# Rx.net
KiCad netlist of a schematic drawn in Altium Designer
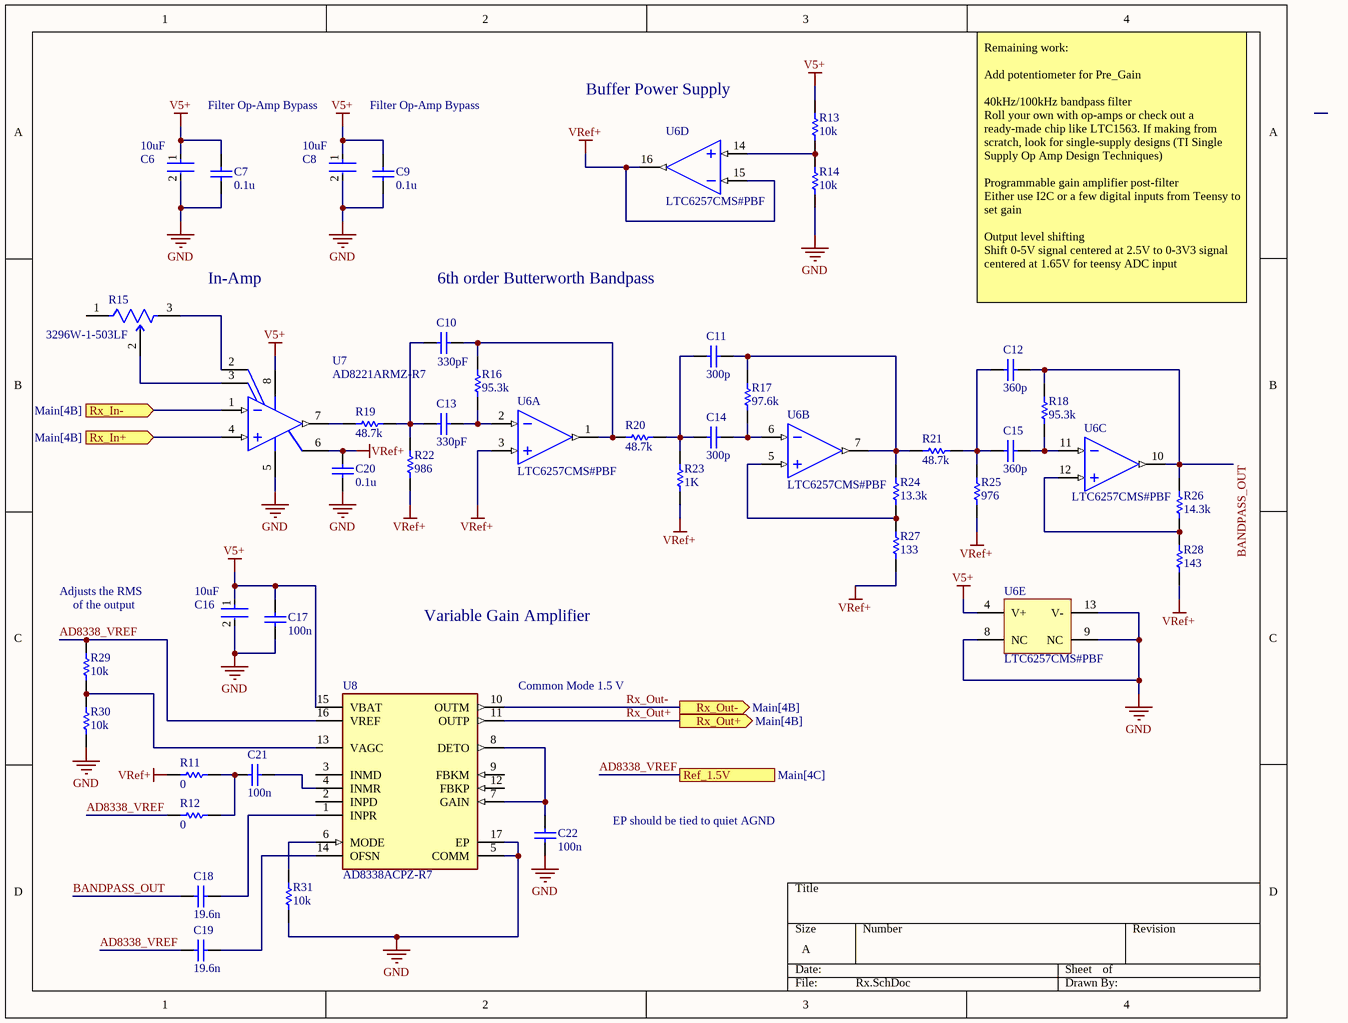
[diagram p0: Rx.SchDoc]

(export (version "E")
  (design (tool "Eeschema 10.0.6"))
  (components
    (comp (ref "C6")
      (value "C3216X5R1H106K160AB")
      (footprint "FP-C3216-160-0_2-IPC_A")
      (description "Multilayer Ceramic Capacitors 10uF ±10% 50V X5R SMD 1206")
      (fields
        (field (name "TOLERANCE") "10%")
        (field (name "VOLTAGE") "50V")
        (field (name "CAPACITANCE") "10uF")
      )
      (libsource (lib "Altium Content Vault") (part "11868f565c42a9108669ba33697ecf6"))
    )
    (comp (ref "C7")
      (value "0.1u")
      (footprint "0805")
      (description "Capacitor")
      (libsource (lib "Simulation Generic Components") (part "Capacitor"))
    )
    (comp (ref "C8")
      (value "C3216X5R1H106K160AB")
      (footprint "FP-C3216-160-0_2-IPC_A")
      (description "Multilayer Ceramic Capacitors 10uF ±10% 50V X5R SMD 1206")
      (fields
        (field (name "TOLERANCE") "10%")
        (field (name "VOLTAGE") "50V")
        (field (name "CAPACITANCE") "10uF")
      )
      (libsource (lib "Altium Content Vault") (part "11868f565c42a9108669ba33697ecf6"))
    )
    (comp (ref "C9")
      (value "0.1u")
      (footprint "0805")
      (description "Capacitor")
      (libsource (lib "Simulation Generic Components") (part "Capacitor"))
    )
    (comp (ref "C10")
      (value "330pF")
      (footprint "0805")
      (description "Capacitor")
      (libsource (lib "Simulation Generic Components") (part "Capacitor"))
    )
    (comp (ref "C11")
      (value "300p")
      (footprint "0805")
      (description "Capacitor")
      (libsource (lib "Simulation Generic Components") (part "Capacitor"))
    )
    (comp (ref "C12")
      (value "360p")
      (footprint "0805")
      (description "Capacitor")
      (libsource (lib "Simulation Generic Components") (part "Capacitor"))
    )
    (comp (ref "C13")
      (value "330pF")
      (footprint "0805")
      (description "Capacitor")
      (libsource (lib "Simulation Generic Components") (part "Capacitor"))
    )
    (comp (ref "C14")
      (value "300p")
      (footprint "0805")
      (description "Capacitor")
      (libsource (lib "Simulation Generic Components") (part "Capacitor"))
    )
    (comp (ref "C15")
      (value "360p")
      (footprint "0805")
      (description "Capacitor")
      (libsource (lib "Simulation Generic Components") (part "Capacitor"))
    )
    (comp (ref "C16")
      (value "C3216X5R1H106K160AB")
      (footprint "FP-C3216-160-0_2-IPC_A")
      (description "Multilayer Ceramic Capacitors 10uF ±10% 50V X5R SMD 1206")
      (fields
        (field (name "TOLERANCE") "10%")
        (field (name "VOLTAGE") "50V")
        (field (name "CAPACITANCE") "10uF")
      )
      (libsource (lib "Altium Content Vault") (part "11868f565c42a9108669ba33697ecf6"))
    )
    (comp (ref "C17")
      (value "100n")
      (footprint "0805")
      (description "Capacitor")
      (libsource (lib "Simulation Generic Components") (part "Capacitor"))
    )
    (comp (ref "C18")
      (value "19.6n")
      (footprint "0805")
      (description "Capacitor")
      (libsource (lib "Simulation Generic Components") (part "Capacitor"))
    )
    (comp (ref "C19")
      (value "19.6n")
      (footprint "0805")
      (description "Capacitor")
      (libsource (lib "Simulation Generic Components") (part "Capacitor"))
    )
    (comp (ref "C20")
      (value "0.1u")
      (footprint "0805")
      (description "Capacitor")
      (libsource (lib "Simulation Generic Components") (part "Capacitor"))
    )
    (comp (ref "C21")
      (value "100n")
      (footprint "0805")
      (description "Capacitor")
      (libsource (lib "Simulation Generic Components") (part "Capacitor"))
    )
    (comp (ref "C22")
      (value "100n")
      (footprint "0805")
      (description "Capacitor")
      (libsource (lib "Simulation Generic Components") (part "Capacitor"))
    )
    (comp (ref "R11")
      (value "0")
      (footprint "0805")
      (description "Resistor")
      (libsource (lib "Simulation Generic Components") (part "Resistor"))
    )
    (comp (ref "R12")
      (value "0")
      (footprint "0805")
      (description "Resistor")
      (libsource (lib "Simulation Generic Components") (part "Resistor"))
    )
    (comp (ref "R13")
      (value "10k")
      (footprint "0805")
      (description "Resistor")
      (libsource (lib "Simulation Generic Components") (part "Resistor"))
    )
    (comp (ref "R14")
      (value "10k")
      (footprint "0805")
      (description "Resistor")
      (libsource (lib "Simulation Generic Components") (part "Resistor"))
    )
    (comp (ref "R15")
      (value "3296W-1-503LF")
      (footprint "FP-3296W-MFG")
      (description "TRIMMER 50K OHM 0.5W PC PIN TOP")
      (fields (field (name "TOLERANCE") "10%"))
      (libsource (lib "Altium Content Vault") (part "2dcfd2547301a7d3209a5e99acfd772"))
    )
    (comp (ref "R16")
      (value "95.3k")
      (footprint "0805")
      (description "Resistor")
      (libsource (lib "Simulation Generic Components") (part "Resistor"))
    )
    (comp (ref "R17")
      (value "97.6k")
      (footprint "0805")
      (description "Resistor")
      (libsource (lib "Simulation Generic Components") (part "Resistor"))
    )
    (comp (ref "R18")
      (value "95.3k")
      (footprint "0805")
      (description "Resistor")
      (libsource (lib "Simulation Generic Components") (part "Resistor"))
    )
    (comp (ref "R19")
      (value "48.7k")
      (footprint "0805")
      (fields
        (field (name "MANUFACTURER") "Panasonic")
        (field (name "MANUFACTURER PART NUMBER") "ERJ-6ENF4872V")
        (field (name "TOLERANCE") "1%")
      )
      (libsource (lib "Simulation Generic Components") (part "Resistor"))
    )
    (comp (ref "R20")
      (value "48.7k")
      (footprint "0805")
      (fields
        (field (name "MANUFACTURER") "Panasonic")
        (field (name "MANUFACTURER PART NUMBER") "ERJ-6ENF4872V")
        (field (name "TOLERANCE") "1%")
      )
      (libsource (lib "Simulation Generic Components") (part "Resistor"))
    )
    (comp (ref "R21")
      (value "48.7k")
      (footprint "0805")
      (description "Resistor")
      (libsource (lib "Simulation Generic Components") (part "Resistor"))
    )
    (comp (ref "R22")
      (value "986")
      (footprint "0805")
      (description "Resistor")
      (libsource (lib "Simulation Generic Components") (part "Resistor"))
    )
    (comp (ref "R23")
      (value "1K")
      (footprint "0805")
      (description "Resistor")
      (libsource (lib "Simulation Generic Components") (part "Resistor"))
    )
    (comp (ref "R24")
      (value "13.3k")
      (footprint "0805")
      (description "Resistor")
      (libsource (lib "Simulation Generic Components") (part "Resistor"))
    )
    (comp (ref "R25")
      (value "976")
      (footprint "0805")
      (description "Resistor")
      (libsource (lib "Simulation Generic Components") (part "Resistor"))
    )
    (comp (ref "R26")
      (value "14.3k")
      (footprint "0805")
      (description "Resistor")
      (libsource (lib "Simulation Generic Components") (part "Resistor"))
    )
    (comp (ref "R27")
      (value "133")
      (footprint "0805")
      (description "Resistor")
      (libsource (lib "Simulation Generic Components") (part "Resistor"))
    )
    (comp (ref "R28")
      (value "143")
      (footprint "0805")
      (description "Resistor")
      (libsource (lib "Simulation Generic Components") (part "Resistor"))
    )
    (comp (ref "R29")
      (value "10k")
      (footprint "0805")
      (description "Resistor")
      (libsource (lib "Simulation Generic Components") (part "Resistor"))
    )
    (comp (ref "R30")
      (value "10k")
      (footprint "0805")
      (description "Resistor")
      (libsource (lib "Simulation Generic Components") (part "Resistor"))
    )
    (comp (ref "R31")
      (value "10k")
      (footprint "0805")
      (description "Resistor")
      (libsource (lib "Simulation Generic Components") (part "Resistor"))
    )
    (comp (ref "U6")
      (value "LTC6257CMS#PBF")
      (footprint "LT-MS-16_N")
      (fields
        (field (name "MANUFACTURER") "Linear Technology")
        (field (name "LINEAR TECHNOLOGY PART NUMBER") "LTC6257")
        (field (name "MANUFACTURER PART NUMBER") "ERJ-6ENF4872V")
      )
      (libsource (lib "") (part "LT-LTC608X-LTC607X-16_1"))
    )
    (comp (ref "U7")
      (value "AD8221ARMZ-R7")
      (footprint "ADI-RM-8_L")
      (fields (field (name "MANUFACTURER") "Analog Devices"))
      (libsource (lib "Altium Content Vault") (part "ADI-AD8221-8"))
    )
    (comp (ref "U8")
      (value "AD8338ACPZ-R7")
      (footprint "FP-CP-16-22-IPC_C")
      (description "IC OPAMP VGA 1 CIRCUIT 16LFCSP")
      (fields
        (field (name "OCTOPART") "https://octopart.com/ad8338acpz-r7-analog+devices-21054770")
        (field (name "MANUFACTURER") "Analog Devices")
      )
      (libsource (lib "Altium Content Vault") (part "4ce7887af0b7713ffabab50ab6d8fb3"))
    )
  )
  (nets
    (net (code "1") (name "/AD8338_VREF") (class "Default")
      (node (ref "C19") (pin "2") (pinfunction "2_2") (pintype "passive"))
      (node (ref "R12") (pin "2") (pinfunction "2_2") (pintype "passive"))
      (node (ref "R29") (pin "2") (pinfunction "2_2") (pintype "passive"))
      (node (ref "U8") (pin "16") (pinfunction "VREF_16") (pintype "power_in"))
    )
    (net (code "2") (name "/BANDPASS_OUT") (class "Default")
      (node (ref "C12") (pin "1") (pinfunction "1_1") (pintype "passive"))
      (node (ref "C18") (pin "2") (pinfunction "2_2") (pintype "passive"))
      (node (ref "R18") (pin "2") (pinfunction "2_2") (pintype "passive"))
      (node (ref "R26") (pin "2") (pinfunction "2_2") (pintype "passive"))
      (node (ref "U6") (pin "10") (pinfunction "OUT_C_10") (pintype "output"))
    )
    (net (code "3") (name "/Rx_In+") (class "Default")
      (node (ref "U7") (pin "4") (pinfunction "IN+_4") (pintype "input"))
    )
    (net (code "4") (name "/Rx_In-") (class "Default")
      (node (ref "U7") (pin "1") (pinfunction "IN-_1") (pintype "input"))
    )
    (net (code "5") (name "/Rx_Out+") (class "Default")
      (node (ref "U8") (pin "11") (pinfunction "OUTP_11") (pintype "output"))
    )
    (net (code "6") (name "/Rx_Out-") (class "Default")
      (node (ref "U8") (pin "10") (pinfunction "OUTM_10") (pintype "output"))
    )
    (net (code "7") (name "GND") (class "Default")
      (node (ref "C16") (pin "2") (pinfunction "2_2") (pintype "passive"))
      (node (ref "C17") (pin "1") (pinfunction "1_1") (pintype "passive"))
      (node (ref "C20") (pin "1") (pinfunction "1_1") (pintype "passive"))
      (node (ref "C22") (pin "1") (pinfunction "1_1") (pintype "passive"))
      (node (ref "C6") (pin "2") (pinfunction "2_2") (pintype "passive"))
      (node (ref "C7") (pin "1") (pinfunction "1_1") (pintype "passive"))
      (node (ref "C8") (pin "2") (pinfunction "2_2") (pintype "passive"))
      (node (ref "C9") (pin "1") (pinfunction "1_1") (pintype "passive"))
      (node (ref "R14") (pin "1") (pinfunction "1_1") (pintype "passive"))
      (node (ref "R30") (pin "1") (pinfunction "1_1") (pintype "passive"))
      (node (ref "R31") (pin "1") (pinfunction "1_1") (pintype "passive"))
      (node (ref "U6") (pin "13") (pinfunction "V-_13") (pintype "power_in"))
      (node (ref "U6") (pin "8") (pinfunction "NC_8") (pintype "passive"))
      (node (ref "U6") (pin "9") (pinfunction "NC_9") (pintype "passive"))
      (node (ref "U7") (pin "5") (pinfunction "VS-_5") (pintype "power_in"))
      (node (ref "U8") (pin "17") (pinfunction "EP_17") (pintype "power_in"))
      (node (ref "U8") (pin "5") (pinfunction "COMM_5") (pintype "power_in"))
    )
    (net (code "8") (name "Net-(C10-Pad2)") (class "Default")
      (node (ref "C10") (pin "2") (pinfunction "2_2") (pintype "passive"))
      (node (ref "C13") (pin "2") (pinfunction "2_2") (pintype "passive"))
      (node (ref "R19") (pin "2") (pinfunction "2_2") (pintype "passive"))
      (node (ref "R22") (pin "2") (pinfunction "2_2") (pintype "passive"))
    )
    (net (code "9") (name "Net-(C11-Pad2)") (class "Default")
      (node (ref "C11") (pin "2") (pinfunction "2_2") (pintype "passive"))
      (node (ref "C14") (pin "2") (pinfunction "2_2") (pintype "passive"))
      (node (ref "R20") (pin "2") (pinfunction "2_2") (pintype "passive"))
      (node (ref "R23") (pin "2") (pinfunction "2_2") (pintype "passive"))
    )
    (net (code "10") (name "Net-(C12-Pad2)") (class "Default")
      (node (ref "C12") (pin "2") (pinfunction "2_2") (pintype "passive"))
      (node (ref "C15") (pin "2") (pinfunction "2_2") (pintype "passive"))
      (node (ref "R21") (pin "2") (pinfunction "2_2") (pintype "passive"))
      (node (ref "R25") (pin "2") (pinfunction "2_2") (pintype "passive"))
    )
    (net (code "11") (name "Net-(C21-Pad2)") (class "Default")
      (node (ref "C21") (pin "2") (pinfunction "2_2") (pintype "passive"))
      (node (ref "R11") (pin "1") (pinfunction "1_1") (pintype "passive"))
      (node (ref "R12") (pin "1") (pinfunction "1_1") (pintype "passive"))
    )
    (net (code "12") (name "Net-(R15-CW)") (class "Default")
      (node (ref "R15") (pin "3") (pinfunction "CW_3") (pintype "passive"))
      (node (ref "U7") (pin "2") (pinfunction "RG_2") (pintype "passive"))
    )
    (net (code "13") (name "Net-(R15-WIPER)") (class "Default")
      (node (ref "R15") (pin "2") (pinfunction "WIPER_2") (pintype "passive"))
      (node (ref "U7") (pin "3") (pinfunction "RG_3") (pintype "passive"))
    )
    (net (code "14") (name "Net-(U6A-IN-_A)") (class "Default")
      (node (ref "C13") (pin "1") (pinfunction "1_1") (pintype "passive"))
      (node (ref "R16") (pin "1") (pinfunction "1_1") (pintype "passive"))
      (node (ref "U6") (pin "2") (pinfunction "IN-_A_2") (pintype "input"))
    )
    (net (code "15") (name "Net-(U6A-OUT_A)") (class "Default")
      (node (ref "C10") (pin "1") (pinfunction "1_1") (pintype "passive"))
      (node (ref "R16") (pin "2") (pinfunction "2_2") (pintype "passive"))
      (node (ref "R20") (pin "1") (pinfunction "1_1") (pintype "passive"))
      (node (ref "U6") (pin "1") (pinfunction "OUT_A_1") (pintype "output"))
    )
    (net (code "16") (name "Net-(U6B-IN+_B)") (class "Default")
      (node (ref "R24") (pin "1") (pinfunction "1_1") (pintype "passive"))
      (node (ref "R27") (pin "2") (pinfunction "2_2") (pintype "passive"))
      (node (ref "U6") (pin "5") (pinfunction "IN+_B_5") (pintype "input"))
    )
    (net (code "17") (name "Net-(U6B-IN-_B)") (class "Default")
      (node (ref "C14") (pin "1") (pinfunction "1_1") (pintype "passive"))
      (node (ref "R17") (pin "1") (pinfunction "1_1") (pintype "passive"))
      (node (ref "U6") (pin "6") (pinfunction "IN-_B_6") (pintype "input"))
    )
    (net (code "18") (name "Net-(U6B-OUT_B)") (class "Default")
      (node (ref "C11") (pin "1") (pinfunction "1_1") (pintype "passive"))
      (node (ref "R17") (pin "2") (pinfunction "2_2") (pintype "passive"))
      (node (ref "R21") (pin "1") (pinfunction "1_1") (pintype "passive"))
      (node (ref "R24") (pin "2") (pinfunction "2_2") (pintype "passive"))
      (node (ref "U6") (pin "7") (pinfunction "OUT_B_7") (pintype "output"))
    )
    (net (code "19") (name "Net-(U6C-IN+_C)") (class "Default")
      (node (ref "R26") (pin "1") (pinfunction "1_1") (pintype "passive"))
      (node (ref "R28") (pin "2") (pinfunction "2_2") (pintype "passive"))
      (node (ref "U6") (pin "12") (pinfunction "IN+_C_12") (pintype "input"))
    )
    (net (code "20") (name "Net-(U6C-IN-_C)") (class "Default")
      (node (ref "C15") (pin "1") (pinfunction "1_1") (pintype "passive"))
      (node (ref "R18") (pin "1") (pinfunction "1_1") (pintype "passive"))
      (node (ref "U6") (pin "11") (pinfunction "IN-_C_11") (pintype "input"))
    )
    (net (code "21") (name "Net-(U6D-IN+_D)") (class "Default")
      (node (ref "R13") (pin "1") (pinfunction "1_1") (pintype "passive"))
      (node (ref "R14") (pin "2") (pinfunction "2_2") (pintype "passive"))
      (node (ref "U6") (pin "14") (pinfunction "IN+_D_14") (pintype "input"))
    )
    (net (code "22") (name "Net-(U7-VOUT)") (class "Default")
      (node (ref "R19") (pin "1") (pinfunction "1_1") (pintype "passive"))
      (node (ref "U7") (pin "7") (pinfunction "VOUT_7") (pintype "output"))
    )
    (net (code "23") (name "Net-(U8-DETO)") (class "Default")
      (node (ref "C22") (pin "2") (pinfunction "2_2") (pintype "passive"))
      (node (ref "U8") (pin "7") (pinfunction "GAIN_7") (pintype "input"))
      (node (ref "U8") (pin "8") (pinfunction "DETO_8") (pintype "output"))
    )
    (net (code "24") (name "Net-(U8-INMR)") (class "Default")
      (node (ref "C21") (pin "1") (pinfunction "1_1") (pintype "passive"))
      (node (ref "U8") (pin "4") (pinfunction "INMR_4") (pintype "passive"))
    )
    (net (code "25") (name "Net-(U8-INPR)") (class "Default")
      (node (ref "C18") (pin "1") (pinfunction "1_1") (pintype "passive"))
      (node (ref "U8") (pin "1") (pinfunction "INPR_1") (pintype "passive"))
    )
    (net (code "26") (name "Net-(U8-MODE)") (class "Default")
      (node (ref "R31") (pin "2") (pinfunction "2_2") (pintype "passive"))
      (node (ref "U8") (pin "6") (pinfunction "MODE_6") (pintype "input"))
    )
    (net (code "27") (name "Net-(U8-OFSN)") (class "Default")
      (node (ref "C19") (pin "1") (pinfunction "1_1") (pintype "passive"))
      (node (ref "U8") (pin "14") (pinfunction "OFSN_14") (pintype "passive"))
    )
    (net (code "28") (name "Net-(U8-VAGC)") (class "Default")
      (node (ref "R29") (pin "1") (pinfunction "1_1") (pintype "passive"))
      (node (ref "R30") (pin "2") (pinfunction "2_2") (pintype "passive"))
      (node (ref "U8") (pin "13") (pinfunction "VAGC_13") (pintype "power_in"))
    )
    (net (code "29") (name "V5+") (class "Default")
      (node (ref "C16") (pin "1") (pinfunction "1_1") (pintype "passive"))
      (node (ref "C17") (pin "2") (pinfunction "2_2") (pintype "passive"))
      (node (ref "C6") (pin "1") (pinfunction "1_1") (pintype "passive"))
      (node (ref "C7") (pin "2") (pinfunction "2_2") (pintype "passive"))
      (node (ref "C8") (pin "1") (pinfunction "1_1") (pintype "passive"))
      (node (ref "C9") (pin "2") (pinfunction "2_2") (pintype "passive"))
      (node (ref "R13") (pin "2") (pinfunction "2_2") (pintype "passive"))
      (node (ref "U6") (pin "4") (pinfunction "V+_4") (pintype "power_in"))
      (node (ref "U7") (pin "8") (pinfunction "VS+_8") (pintype "power_in"))
      (node (ref "U8") (pin "15") (pinfunction "VBAT_15") (pintype "power_in"))
    )
    (net (code "30") (name "VRef+") (class "Default")
      (node (ref "C20") (pin "2") (pinfunction "2_2") (pintype "passive"))
      (node (ref "R11") (pin "2") (pinfunction "2_2") (pintype "passive"))
      (node (ref "R22") (pin "1") (pinfunction "1_1") (pintype "passive"))
      (node (ref "R23") (pin "1") (pinfunction "1_1") (pintype "passive"))
      (node (ref "R25") (pin "1") (pinfunction "1_1") (pintype "passive"))
      (node (ref "R27") (pin "1") (pinfunction "1_1") (pintype "passive"))
      (node (ref "R28") (pin "1") (pinfunction "1_1") (pintype "passive"))
      (node (ref "U6") (pin "15") (pinfunction "IN-_D_15") (pintype "input"))
      (node (ref "U6") (pin "16") (pinfunction "OUT_D_16") (pintype "output"))
      (node (ref "U6") (pin "3") (pinfunction "IN+_A_3") (pintype "input"))
      (node (ref "U7") (pin "6") (pinfunction "REF_6") (pintype "passive"))
    )
    (net (code "31") (name "unconnected-(R15-CCW-Pad1)") (class "Default")
      (node (ref "R15") (pin "1") (pinfunction "CCW_1") (pintype "passive"))
    )
    (net (code "32") (name "unconnected-(U8-FBKM-Pad9)") (class "Default")
      (node (ref "U8") (pin "9") (pinfunction "FBKM_9") (pintype "input"))
    )
    (net (code "33") (name "unconnected-(U8-FBKP-Pad12)") (class "Default")
      (node (ref "U8") (pin "12") (pinfunction "FBKP_12") (pintype "input"))
    )
    (net (code "34") (name "unconnected-(U8-INMD-Pad3)") (class "Default")
      (node (ref "U8") (pin "3") (pinfunction "INMD_3") (pintype "passive"))
    )
    (net (code "35") (name "unconnected-(U8-INPD-Pad2)") (class "Default")
      (node (ref "U8") (pin "2") (pinfunction "INPD_2") (pintype "passive"))
    )
  )
)
